# RS422_Breakout.net
KiCad netlist of a schematic drawn in Altium Designer
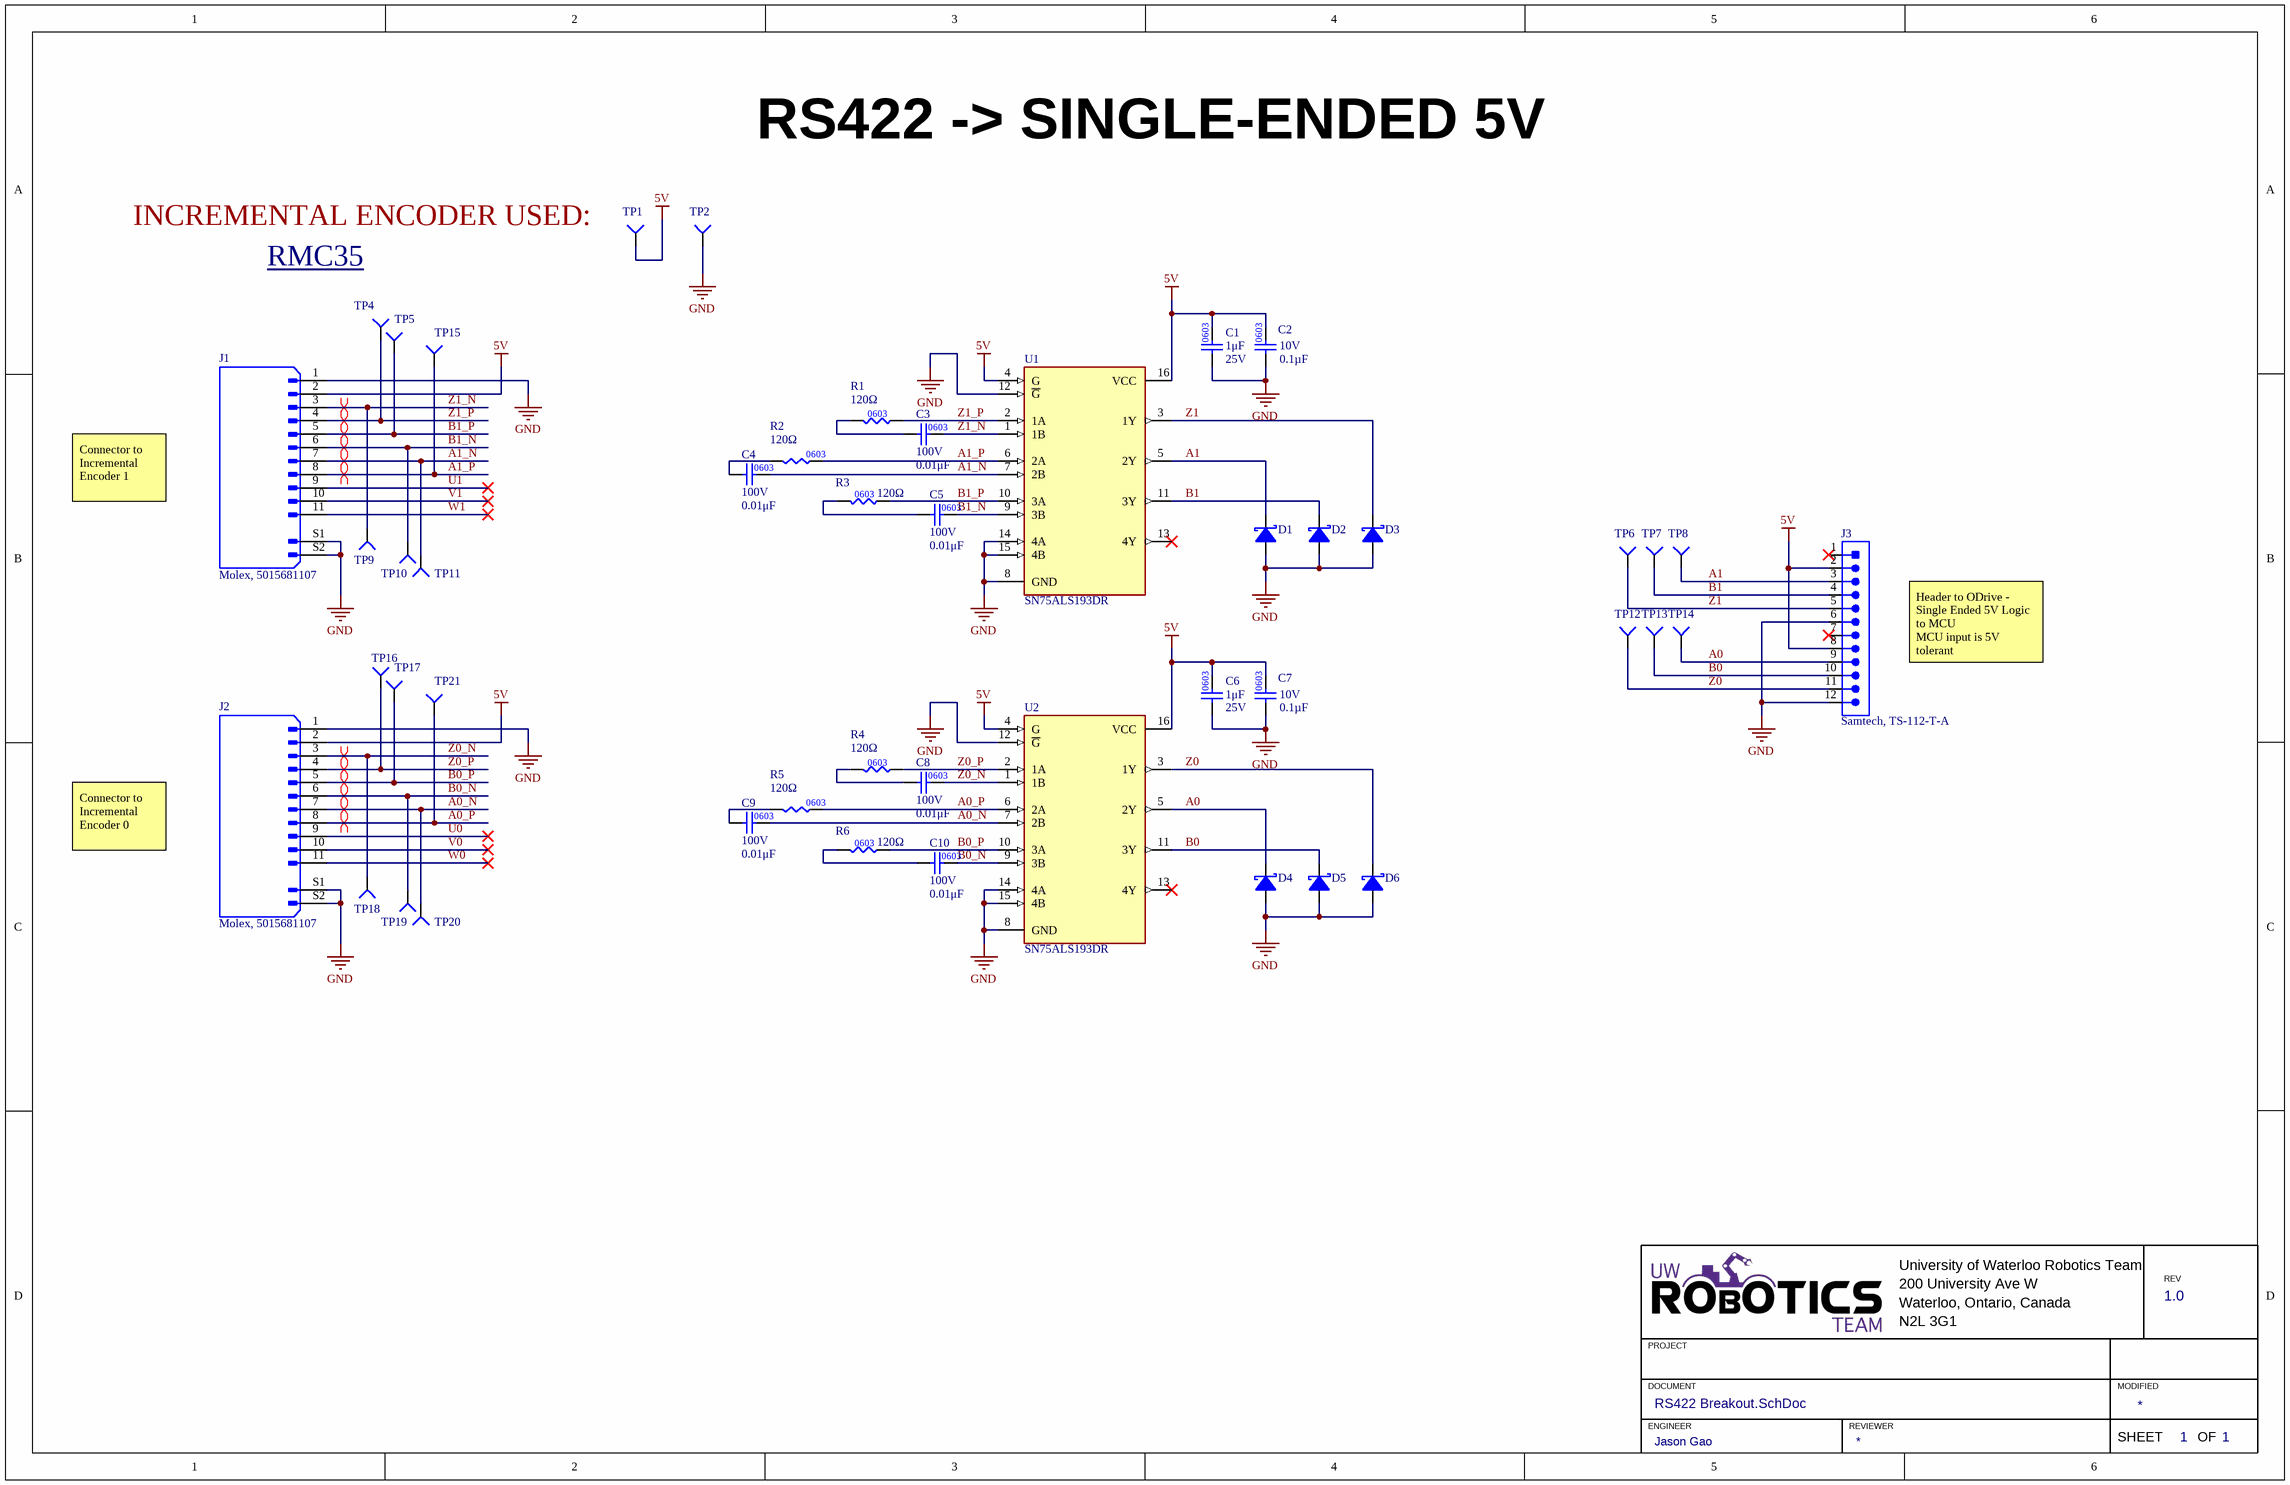
[diagram p0: RS422 Breakout.SchDoc]

(export (version "E")
  (design (tool "Eeschema 10.0.6"))
  (components
    (comp (ref "C1")
      (value "1μF")
      (footprint "CAP0603")
      (description "CAP CER 1UF 25V X5R 0603")
      (fields (field (name "VOLTAGE RATING") "25V") (field (name "Comment") "CAP_1uF_25V_0603"))
      (libsource (lib "UWRT_Schematic_Library_2020") (part "CAP_1uF_25V_0603"))
    )
    (comp (ref "C2")
      (value "0.1µF")
      (footprint "CAP0603")
      (description "CAP CER 0.1UF 10V X7R 0402")
      (fields (field (name "VOLTAGE RATING") "10V") (field (name "Comment") "CAP_0.1uF_10V_0603"))
      (libsource (lib "UWRT_Schematic_Library_2020") (part "CAP_0.1uF_10V_0603"))
    )
    (comp (ref "C3")
      (value "0.01μF")
      (footprint "CAP0603")
      (description "CAP CER 0.01uF 100V X7R 0603")
      (fields (field (name "VOLTAGE RATING") "100V") (field (name "Comment") "CAP_0.01uF_100V_0603"))
      (libsource (lib "UWRT_Schematic_Library_2020") (part "CAP_0.01uF_100V_0603"))
    )
    (comp (ref "C4")
      (value "0.01μF")
      (footprint "CAP0603")
      (description "CAP CER 0.01uF 100V X7R 0603")
      (fields (field (name "VOLTAGE RATING") "100V") (field (name "Comment") "CAP_0.01uF_100V_0603"))
      (libsource (lib "UWRT_Schematic_Library_2020") (part "CAP_0.01uF_100V_0603"))
    )
    (comp (ref "C5")
      (value "0.01μF")
      (footprint "CAP0603")
      (description "CAP CER 0.01uF 100V X7R 0603")
      (fields (field (name "VOLTAGE RATING") "100V") (field (name "Comment") "CAP_0.01uF_100V_0603"))
      (libsource (lib "UWRT_Schematic_Library_2020") (part "CAP_0.01uF_100V_0603"))
    )
    (comp (ref "C6")
      (value "1μF")
      (footprint "CAP0603")
      (description "CAP CER 1UF 25V X5R 0603")
      (fields (field (name "VOLTAGE RATING") "25V") (field (name "Comment") "CAP_1uF_25V_0603"))
      (libsource (lib "UWRT_Schematic_Library_2020") (part "CAP_1uF_25V_0603"))
    )
    (comp (ref "C7")
      (value "0.1µF")
      (footprint "CAP0603")
      (description "CAP CER 0.1UF 10V X7R 0402")
      (fields (field (name "VOLTAGE RATING") "10V") (field (name "Comment") "CAP_0.1uF_10V_0603"))
      (libsource (lib "UWRT_Schematic_Library_2020") (part "CAP_0.1uF_10V_0603"))
    )
    (comp (ref "C8")
      (value "0.01μF")
      (footprint "CAP0603")
      (description "CAP CER 0.01uF 100V X7R 0603")
      (fields (field (name "VOLTAGE RATING") "100V") (field (name "Comment") "CAP_0.01uF_100V_0603"))
      (libsource (lib "UWRT_Schematic_Library_2020") (part "CAP_0.01uF_100V_0603"))
    )
    (comp (ref "C9")
      (value "0.01μF")
      (footprint "CAP0603")
      (description "CAP CER 0.01uF 100V X7R 0603")
      (fields (field (name "VOLTAGE RATING") "100V") (field (name "Comment") "CAP_0.01uF_100V_0603"))
      (libsource (lib "UWRT_Schematic_Library_2020") (part "CAP_0.01uF_100V_0603"))
    )
    (comp (ref "C10")
      (value "0.01μF")
      (footprint "CAP0603")
      (description "CAP CER 0.01uF 100V X7R 0603")
      (fields (field (name "VOLTAGE RATING") "100V") (field (name "Comment") "CAP_0.01uF_100V_0603"))
      (libsource (lib "UWRT_Schematic_Library_2020") (part "CAP_0.01uF_100V_0603"))
    )
    (comp (ref "D1")
      (value "TVS_DIODE_UNIDIR_5V")
      (footprint "sod-923")
      (description "TVS DIODE 5VWM 12.3VC SOD923")
      (libsource (lib "UWRT_Schematic_Library_2020") (part "TVS_DIODE_UNIDIR_5V"))
    )
    (comp (ref "D2")
      (value "TVS_DIODE_UNIDIR_5V")
      (footprint "sod-923")
      (description "TVS DIODE 5VWM 12.3VC SOD923")
      (libsource (lib "UWRT_Schematic_Library_2020") (part "TVS_DIODE_UNIDIR_5V"))
    )
    (comp (ref "D3")
      (value "TVS_DIODE_UNIDIR_5V")
      (footprint "sod-923")
      (description "TVS DIODE 5VWM 12.3VC SOD923")
      (libsource (lib "UWRT_Schematic_Library_2020") (part "TVS_DIODE_UNIDIR_5V"))
    )
    (comp (ref "D4")
      (value "TVS_DIODE_UNIDIR_5V")
      (footprint "sod-923")
      (description "TVS DIODE 5VWM 12.3VC SOD923")
      (libsource (lib "UWRT_Schematic_Library_2020") (part "TVS_DIODE_UNIDIR_5V"))
    )
    (comp (ref "D5")
      (value "TVS_DIODE_UNIDIR_5V")
      (footprint "sod-923")
      (description "TVS DIODE 5VWM 12.3VC SOD923")
      (libsource (lib "UWRT_Schematic_Library_2020") (part "TVS_DIODE_UNIDIR_5V"))
    )
    (comp (ref "D6")
      (value "TVS_DIODE_UNIDIR_5V")
      (footprint "sod-923")
      (description "TVS DIODE 5VWM 12.3VC SOD923")
      (libsource (lib "UWRT_Schematic_Library_2020") (part "TVS_DIODE_UNIDIR_5V"))
    )
    (comp (ref "J1")
      (value "CON_12M_SM_RA")
      (footprint "MOLEX-5015681107")
      (description "CONN HEADER SMD RIGHT ANGLE 1MM PITCH")
      (fields (field (name "MP") "Molex, 5015681107"))
      (libsource (lib "templocal") (part "CON_11M_SM_RA"))
    )
    (comp (ref "J2")
      (value "CON_12M_SM_RA")
      (footprint "MOLEX-5015681107")
      (description "CONN HEADER SMD RIGHT ANGLE 1MM PITCH")
      (fields (field (name "MP") "Molex, 5015681107"))
      (libsource (lib "templocal") (part "CON_11M_SM_RA"))
    )
    (comp (ref "J3")
      (value "Samtech, TS-112-T-A")
      (footprint "Samtech-TS-112-T-A")
      (description "CONN HEADER THROUGH HOLE VERTICAL 2.54MM PITCH")
      (fields (field (name "MANUFACTURING PART NUMBER") "Samtech, TS-112-T-A"))
      (libsource (lib "UWRT_Schematic_Library_2020") (part "CON_12M_TH_VERT_2.54mm"))
    )
    (comp (ref "R1")
      (value "120Ω")
      (footprint "RES0603")
      (description "RES 120 OHM 5% 1/10W 0603")
      (fields (field (name "Comment") "RES_120Ω_0603_5%"))
      (libsource (lib "UWRT_Schematic_Library_2020") (part "RES_120Ω_0603_5%"))
    )
    (comp (ref "R2")
      (value "120Ω")
      (footprint "RES0603")
      (description "RES 120 OHM 5% 1/10W 0603")
      (fields (field (name "Comment") "RES_120Ω_0603_5%"))
      (libsource (lib "UWRT_Schematic_Library_2020") (part "RES_120Ω_0603_5%"))
    )
    (comp (ref "R3")
      (value "120Ω")
      (footprint "RES0603")
      (description "RES 120 OHM 5% 1/10W 0603")
      (fields (field (name "Comment") "RES_120Ω_0603_5%"))
      (libsource (lib "UWRT_Schematic_Library_2020") (part "RES_120Ω_0603_5%"))
    )
    (comp (ref "R4")
      (value "120Ω")
      (footprint "RES0603")
      (description "RES 120 OHM 5% 1/10W 0603")
      (fields (field (name "Comment") "RES_120Ω_0603_5%"))
      (libsource (lib "UWRT_Schematic_Library_2020") (part "RES_120Ω_0603_5%"))
    )
    (comp (ref "R5")
      (value "120Ω")
      (footprint "RES0603")
      (description "RES 120 OHM 5% 1/10W 0603")
      (fields (field (name "Comment") "RES_120Ω_0603_5%"))
      (libsource (lib "UWRT_Schematic_Library_2020") (part "RES_120Ω_0603_5%"))
    )
    (comp (ref "R6")
      (value "120Ω")
      (footprint "RES0603")
      (description "RES 120 OHM 5% 1/10W 0603")
      (fields (field (name "Comment") "RES_120Ω_0603_5%"))
      (libsource (lib "UWRT_Schematic_Library_2020") (part "RES_120Ω_0603_5%"))
    )
    (comp (ref "TP1")
      (value "TESTPOINT_SMD_LOOP")
      (footprint "S1751-46R")
      (description "TESTPOINT SMD LOOP")
      (libsource (lib "UWRT_Schematic_Library_2020") (part "TESTPOINT_SMD_LOOP"))
    )
    (comp (ref "TP2")
      (value "TESTPOINT_SMD_LOOP")
      (footprint "S1751-46R")
      (description "TESTPOINT SMD LOOP")
      (libsource (lib "UWRT_Schematic_Library_2020") (part "TESTPOINT_SMD_LOOP"))
    )
    (comp (ref "TP4")
      (value "TESTPOINT_1MM_SQUARE")
      (footprint "TESTPOINT_SQUARE_1MM")
      (description "TESTPOINT 1MM SQUARE")
      (libsource (lib "UWRT_Schematic_Library_2020") (part "TESTPOINT_1MM_SQUARE"))
    )
    (comp (ref "TP5")
      (value "TESTPOINT_1MM_SQUARE")
      (footprint "TESTPOINT_SQUARE_1MM")
      (description "TESTPOINT 1MM SQUARE")
      (libsource (lib "UWRT_Schematic_Library_2020") (part "TESTPOINT_1MM_SQUARE"))
    )
    (comp (ref "TP6")
      (value "TESTPOINT_1MM_CIRCLE")
      (footprint "TESTPOINT_CIRCLE_1MM")
      (description "TESTPOINT 1MM CIRCLE")
      (libsource (lib "UWRT_Schematic_Library_2020") (part "TESTPOINT_1MM_CIRCLE"))
    )
    (comp (ref "TP7")
      (value "TESTPOINT_1MM_CIRCLE")
      (footprint "TESTPOINT_CIRCLE_1MM")
      (description "TESTPOINT 1MM CIRCLE")
      (libsource (lib "UWRT_Schematic_Library_2020") (part "TESTPOINT_1MM_CIRCLE"))
    )
    (comp (ref "TP8")
      (value "TESTPOINT_1MM_CIRCLE")
      (footprint "TESTPOINT_CIRCLE_1MM")
      (description "TESTPOINT 1MM CIRCLE")
      (libsource (lib "UWRT_Schematic_Library_2020") (part "TESTPOINT_1MM_CIRCLE"))
    )
    (comp (ref "TP9")
      (value "TESTPOINT_1MM_CIRCLE")
      (footprint "TESTPOINT_CIRCLE_1MM")
      (description "TESTPOINT 1MM CIRCLE")
      (libsource (lib "UWRT_Schematic_Library_2020") (part "TESTPOINT_1MM_CIRCLE"))
    )
    (comp (ref "TP10")
      (value "TESTPOINT_1MM_CIRCLE")
      (footprint "TESTPOINT_CIRCLE_1MM")
      (description "TESTPOINT 1MM CIRCLE")
      (libsource (lib "UWRT_Schematic_Library_2020") (part "TESTPOINT_1MM_CIRCLE"))
    )
    (comp (ref "TP11")
      (value "TESTPOINT_1MM_CIRCLE")
      (footprint "TESTPOINT_CIRCLE_1MM")
      (description "TESTPOINT 1MM CIRCLE")
      (libsource (lib "UWRT_Schematic_Library_2020") (part "TESTPOINT_1MM_CIRCLE"))
    )
    (comp (ref "TP12")
      (value "TESTPOINT_1MM_CIRCLE")
      (footprint "TESTPOINT_CIRCLE_1MM")
      (description "TESTPOINT 1MM CIRCLE")
      (libsource (lib "UWRT_Schematic_Library_2020") (part "TESTPOINT_1MM_CIRCLE"))
    )
    (comp (ref "TP13")
      (value "TESTPOINT_1MM_CIRCLE")
      (footprint "TESTPOINT_CIRCLE_1MM")
      (description "TESTPOINT 1MM CIRCLE")
      (libsource (lib "UWRT_Schematic_Library_2020") (part "TESTPOINT_1MM_CIRCLE"))
    )
    (comp (ref "TP14")
      (value "TESTPOINT_1MM_CIRCLE")
      (footprint "TESTPOINT_CIRCLE_1MM")
      (description "TESTPOINT 1MM CIRCLE")
      (libsource (lib "UWRT_Schematic_Library_2020") (part "TESTPOINT_1MM_CIRCLE"))
    )
    (comp (ref "TP15")
      (value "TESTPOINT_1MM_SQUARE")
      (footprint "TESTPOINT_SQUARE_1MM")
      (description "TESTPOINT 1MM SQUARE")
      (libsource (lib "UWRT_Schematic_Library_2020") (part "TESTPOINT_1MM_SQUARE"))
    )
    (comp (ref "TP16")
      (value "TESTPOINT_1MM_SQUARE")
      (footprint "TESTPOINT_SQUARE_1MM")
      (description "TESTPOINT 1MM SQUARE")
      (libsource (lib "UWRT_Schematic_Library_2020") (part "TESTPOINT_1MM_SQUARE"))
    )
    (comp (ref "TP17")
      (value "TESTPOINT_1MM_SQUARE")
      (footprint "TESTPOINT_SQUARE_1MM")
      (description "TESTPOINT 1MM SQUARE")
      (libsource (lib "UWRT_Schematic_Library_2020") (part "TESTPOINT_1MM_SQUARE"))
    )
    (comp (ref "TP18")
      (value "TESTPOINT_1MM_CIRCLE")
      (footprint "TESTPOINT_CIRCLE_1MM")
      (description "TESTPOINT 1MM CIRCLE")
      (libsource (lib "UWRT_Schematic_Library_2020") (part "TESTPOINT_1MM_CIRCLE"))
    )
    (comp (ref "TP19")
      (value "TESTPOINT_1MM_CIRCLE")
      (footprint "TESTPOINT_CIRCLE_1MM")
      (description "TESTPOINT 1MM CIRCLE")
      (libsource (lib "UWRT_Schematic_Library_2020") (part "TESTPOINT_1MM_CIRCLE"))
    )
    (comp (ref "TP20")
      (value "TESTPOINT_1MM_CIRCLE")
      (footprint "TESTPOINT_CIRCLE_1MM")
      (description "TESTPOINT 1MM CIRCLE")
      (libsource (lib "UWRT_Schematic_Library_2020") (part "TESTPOINT_1MM_CIRCLE"))
    )
    (comp (ref "TP21")
      (value "TESTPOINT_1MM_SQUARE")
      (footprint "TESTPOINT_SQUARE_1MM")
      (description "TESTPOINT 1MM SQUARE")
      (libsource (lib "UWRT_Schematic_Library_2020") (part "TESTPOINT_1MM_SQUARE"))
    )
    (comp (ref "U1")
      (value "SN75ALS193DR")
      (footprint "SOIC127P600X175-16N")
      (description "0/4 Receiver - RS422, RS423 16-SOIC")
      (fields (field (name "COPYRIGHT") "Copyright (C) 2021 Ultra Librarian. All rights reserved."))
      (libsource (lib "UWRT_Schematic_Library_2020") (part "SN75ALS193DR"))
    )
    (comp (ref "U2")
      (value "SN75ALS193DR")
      (footprint "SOIC127P600X175-16N")
      (description "0/4 Receiver - RS422, RS423 16-SOIC")
      (fields (field (name "COPYRIGHT") "Copyright (C) 2021 Ultra Librarian. All rights reserved."))
      (libsource (lib "UWRT_Schematic_Library_2020") (part "SN75ALS193DR"))
    )
  )
  (nets
    (net (code "1") (name "/A0") (class "Default")
      (node (ref "D4") (pin "1") (pinfunction "Cathode_1") (pintype "passive"))
      (node (ref "J3") (pin "9") (pinfunction "3_9") (pintype "passive"))
      (node (ref "TP14") (pin "1") (pinfunction "=value_1") (pintype "passive"))
      (node (ref "U2") (pin "5") (pinfunction "2Y_5") (pintype "output"))
    )
    (net (code "2") (name "/A0_N") (class "Default")
      (node (ref "C9") (pin "2") (pinfunction "2_2") (pintype "passive"))
      (node (ref "J2") (pin "7") (pinfunction "7_7") (pintype "passive"))
      (node (ref "TP20") (pin "1") (pinfunction "=value_1") (pintype "passive"))
      (node (ref "U2") (pin "7") (pinfunction "2B_7") (pintype "input"))
    )
    (net (code "3") (name "/A0_P") (class "Default")
      (node (ref "J2") (pin "8") (pinfunction "8_8") (pintype "passive"))
      (node (ref "R5") (pin "2") (pinfunction "2_2") (pintype "passive"))
      (node (ref "TP21") (pin "1") (pinfunction "=value_1") (pintype "passive"))
      (node (ref "U2") (pin "6") (pinfunction "2A_6") (pintype "input"))
    )
    (net (code "4") (name "/A1") (class "Default")
      (node (ref "D1") (pin "1") (pinfunction "Cathode_1") (pintype "passive"))
      (node (ref "J3") (pin "3") (pinfunction "3_3") (pintype "passive"))
      (node (ref "TP8") (pin "1") (pinfunction "=value_1") (pintype "passive"))
      (node (ref "U1") (pin "5") (pinfunction "2Y_5") (pintype "output"))
    )
    (net (code "5") (name "/A1_N") (class "Default")
      (node (ref "C4") (pin "2") (pinfunction "2_2") (pintype "passive"))
      (node (ref "J1") (pin "7") (pinfunction "7_7") (pintype "passive"))
      (node (ref "TP11") (pin "1") (pinfunction "=value_1") (pintype "passive"))
      (node (ref "U1") (pin "7") (pinfunction "2B_7") (pintype "input"))
    )
    (net (code "6") (name "/A1_P") (class "Default")
      (node (ref "J1") (pin "8") (pinfunction "8_8") (pintype "passive"))
      (node (ref "R2") (pin "2") (pinfunction "2_2") (pintype "passive"))
      (node (ref "TP15") (pin "1") (pinfunction "=value_1") (pintype "passive"))
      (node (ref "U1") (pin "6") (pinfunction "2A_6") (pintype "input"))
    )
    (net (code "7") (name "/B0") (class "Default")
      (node (ref "D5") (pin "1") (pinfunction "Cathode_1") (pintype "passive"))
      (node (ref "J3") (pin "10") (pinfunction "4_10") (pintype "passive"))
      (node (ref "TP13") (pin "1") (pinfunction "=value_1") (pintype "passive"))
      (node (ref "U2") (pin "11") (pinfunction "3Y_11") (pintype "output"))
    )
    (net (code "8") (name "/B0_N") (class "Default")
      (node (ref "C10") (pin "2") (pinfunction "2_2") (pintype "passive"))
      (node (ref "J2") (pin "6") (pinfunction "6_6") (pintype "passive"))
      (node (ref "TP19") (pin "1") (pinfunction "=value_1") (pintype "passive"))
      (node (ref "U2") (pin "9") (pinfunction "3B_9") (pintype "input"))
    )
    (net (code "9") (name "/B0_P") (class "Default")
      (node (ref "J2") (pin "5") (pinfunction "5_5") (pintype "passive"))
      (node (ref "R6") (pin "1") (pinfunction "1_1") (pintype "passive"))
      (node (ref "TP17") (pin "1") (pinfunction "=value_1") (pintype "passive"))
      (node (ref "U2") (pin "10") (pinfunction "3A_10") (pintype "input"))
    )
    (net (code "10") (name "/B1") (class "Default")
      (node (ref "D2") (pin "1") (pinfunction "Cathode_1") (pintype "passive"))
      (node (ref "J3") (pin "4") (pinfunction "4_4") (pintype "passive"))
      (node (ref "TP7") (pin "1") (pinfunction "=value_1") (pintype "passive"))
      (node (ref "U1") (pin "11") (pinfunction "3Y_11") (pintype "output"))
    )
    (net (code "11") (name "/B1_N") (class "Default")
      (node (ref "C5") (pin "2") (pinfunction "2_2") (pintype "passive"))
      (node (ref "J1") (pin "6") (pinfunction "6_6") (pintype "passive"))
      (node (ref "TP10") (pin "1") (pinfunction "=value_1") (pintype "passive"))
      (node (ref "U1") (pin "9") (pinfunction "3B_9") (pintype "input"))
    )
    (net (code "12") (name "/B1_P") (class "Default")
      (node (ref "J1") (pin "5") (pinfunction "5_5") (pintype "passive"))
      (node (ref "R3") (pin "1") (pinfunction "1_1") (pintype "passive"))
      (node (ref "TP5") (pin "1") (pinfunction "=value_1") (pintype "passive"))
      (node (ref "U1") (pin "10") (pinfunction "3A_10") (pintype "input"))
    )
    (net (code "13") (name "/U0") (class "Default")
      (node (ref "J2") (pin "9") (pinfunction "9_9") (pintype "passive+no_connect"))
    )
    (net (code "14") (name "/U1") (class "Default")
      (node (ref "J1") (pin "9") (pinfunction "9_9") (pintype "passive+no_connect"))
    )
    (net (code "15") (name "/V0") (class "Default")
      (node (ref "J2") (pin "10") (pinfunction "10_10") (pintype "passive+no_connect"))
    )
    (net (code "16") (name "/V1") (class "Default")
      (node (ref "J1") (pin "10") (pinfunction "10_10") (pintype "passive+no_connect"))
    )
    (net (code "17") (name "/W0") (class "Default")
      (node (ref "J2") (pin "11") (pinfunction "11_11") (pintype "passive+no_connect"))
    )
    (net (code "18") (name "/W1") (class "Default")
      (node (ref "J1") (pin "11") (pinfunction "11_11") (pintype "passive+no_connect"))
    )
    (net (code "19") (name "/Z0") (class "Default")
      (node (ref "D6") (pin "1") (pinfunction "Cathode_1") (pintype "passive"))
      (node (ref "J3") (pin "11") (pinfunction "5_11") (pintype "passive"))
      (node (ref "TP12") (pin "1") (pinfunction "=value_1") (pintype "passive"))
      (node (ref "U2") (pin "3") (pinfunction "1Y_3") (pintype "output"))
    )
    (net (code "20") (name "/Z0_N") (class "Default")
      (node (ref "C8") (pin "2") (pinfunction "2_2") (pintype "passive"))
      (node (ref "J2") (pin "3") (pinfunction "3_3") (pintype "passive"))
      (node (ref "TP18") (pin "1") (pinfunction "=value_1") (pintype "passive"))
      (node (ref "U2") (pin "1") (pinfunction "1B_1") (pintype "input"))
    )
    (net (code "21") (name "/Z0_P") (class "Default")
      (node (ref "J2") (pin "4") (pinfunction "4_4") (pintype "passive"))
      (node (ref "R4") (pin "1") (pinfunction "1_1") (pintype "passive"))
      (node (ref "TP16") (pin "1") (pinfunction "=value_1") (pintype "passive"))
      (node (ref "U2") (pin "2") (pinfunction "1A_2") (pintype "input"))
    )
    (net (code "22") (name "/Z1") (class "Default")
      (node (ref "D3") (pin "1") (pinfunction "Cathode_1") (pintype "passive"))
      (node (ref "J3") (pin "5") (pinfunction "5_5") (pintype "passive"))
      (node (ref "TP6") (pin "1") (pinfunction "=value_1") (pintype "passive"))
      (node (ref "U1") (pin "3") (pinfunction "1Y_3") (pintype "output"))
    )
    (net (code "23") (name "/Z1_N") (class "Default")
      (node (ref "C3") (pin "2") (pinfunction "2_2") (pintype "passive"))
      (node (ref "J1") (pin "3") (pinfunction "3_3") (pintype "passive"))
      (node (ref "TP9") (pin "1") (pinfunction "=value_1") (pintype "passive"))
      (node (ref "U1") (pin "1") (pinfunction "1B_1") (pintype "input"))
    )
    (net (code "24") (name "/Z1_P") (class "Default")
      (node (ref "J1") (pin "4") (pinfunction "4_4") (pintype "passive"))
      (node (ref "R1") (pin "1") (pinfunction "1_1") (pintype "passive"))
      (node (ref "TP4") (pin "1") (pinfunction "=value_1") (pintype "passive"))
      (node (ref "U1") (pin "2") (pinfunction "1A_2") (pintype "input"))
    )
    (net (code "25") (name "5V") (class "Default")
      (node (ref "C1") (pin "2") (pinfunction "2_2") (pintype "passive"))
      (node (ref "C2") (pin "2") (pinfunction "2_2") (pintype "passive"))
      (node (ref "C6") (pin "2") (pinfunction "2_2") (pintype "passive"))
      (node (ref "C7") (pin "2") (pinfunction "2_2") (pintype "passive"))
      (node (ref "J1") (pin "2") (pinfunction "2_2") (pintype "passive"))
      (node (ref "J2") (pin "2") (pinfunction "2_2") (pintype "passive"))
      (node (ref "J3") (pin "2") (pinfunction "2_2") (pintype "passive"))
      (node (ref "J3") (pin "8") (pinfunction "2_8") (pintype "passive"))
      (node (ref "TP1") (pin "1") (pinfunction "=value_1") (pintype "passive"))
      (node (ref "U1") (pin "16") (pinfunction "VCC_16") (pintype "power_in"))
      (node (ref "U1") (pin "4") (pinfunction "G_4") (pintype "input"))
      (node (ref "U2") (pin "16") (pinfunction "VCC_16") (pintype "power_in"))
      (node (ref "U2") (pin "4") (pinfunction "G_4") (pintype "input"))
    )
    (net (code "26") (name "GND") (class "Default")
      (node (ref "C1") (pin "1") (pinfunction "1_1") (pintype "passive"))
      (node (ref "C2") (pin "1") (pinfunction "1_1") (pintype "passive"))
      (node (ref "C6") (pin "1") (pinfunction "1_1") (pintype "passive"))
      (node (ref "C7") (pin "1") (pinfunction "1_1") (pintype "passive"))
      (node (ref "D1") (pin "2") (pinfunction "Anode_2") (pintype "passive"))
      (node (ref "D2") (pin "2") (pinfunction "Anode_2") (pintype "passive"))
      (node (ref "D3") (pin "2") (pinfunction "Anode_2") (pintype "passive"))
      (node (ref "D4") (pin "2") (pinfunction "Anode_2") (pintype "passive"))
      (node (ref "D5") (pin "2") (pinfunction "Anode_2") (pintype "passive"))
      (node (ref "D6") (pin "2") (pinfunction "Anode_2") (pintype "passive"))
      (node (ref "J1") (pin "1") (pinfunction "1_1") (pintype "passive"))
      (node (ref "J1") (pin "S1") (pinfunction "SHIELD1_S1") (pintype "passive"))
      (node (ref "J1") (pin "S2") (pinfunction "SHIELD2_S2") (pintype "passive"))
      (node (ref "J2") (pin "1") (pinfunction "1_1") (pintype "passive"))
      (node (ref "J2") (pin "S1") (pinfunction "SHIELD1_S1") (pintype "passive"))
      (node (ref "J2") (pin "S2") (pinfunction "SHIELD2_S2") (pintype "passive"))
      (node (ref "J3") (pin "12") (pinfunction "6_12") (pintype "passive"))
      (node (ref "J3") (pin "6") (pinfunction "6_6") (pintype "passive"))
      (node (ref "TP2") (pin "1") (pinfunction "=value_1") (pintype "passive"))
      (node (ref "U1") (pin "12") (pinfunction "~{G}_12") (pintype "input"))
      (node (ref "U1") (pin "14") (pinfunction "4A_14") (pintype "input"))
      (node (ref "U1") (pin "15") (pinfunction "4B_15") (pintype "input"))
      (node (ref "U1") (pin "8") (pinfunction "GND_8") (pintype "power_in"))
      (node (ref "U2") (pin "12") (pinfunction "~{G}_12") (pintype "input"))
      (node (ref "U2") (pin "14") (pinfunction "4A_14") (pintype "input"))
      (node (ref "U2") (pin "15") (pinfunction "4B_15") (pintype "input"))
      (node (ref "U2") (pin "8") (pinfunction "GND_8") (pintype "power_in"))
    )
    (net (code "27") (name "Net-(C3-Pad1)") (class "Default")
      (node (ref "C3") (pin "1") (pinfunction "1_1") (pintype "passive"))
      (node (ref "R1") (pin "2") (pinfunction "2_2") (pintype "passive"))
    )
    (net (code "28") (name "Net-(C4-Pad1)") (class "Default")
      (node (ref "C4") (pin "1") (pinfunction "1_1") (pintype "passive"))
      (node (ref "R2") (pin "1") (pinfunction "1_1") (pintype "passive"))
    )
    (net (code "29") (name "Net-(C5-Pad1)") (class "Default")
      (node (ref "C5") (pin "1") (pinfunction "1_1") (pintype "passive"))
      (node (ref "R3") (pin "2") (pinfunction "2_2") (pintype "passive"))
    )
    (net (code "30") (name "Net-(C8-Pad1)") (class "Default")
      (node (ref "C8") (pin "1") (pinfunction "1_1") (pintype "passive"))
      (node (ref "R4") (pin "2") (pinfunction "2_2") (pintype "passive"))
    )
    (net (code "31") (name "Net-(C9-Pad1)") (class "Default")
      (node (ref "C9") (pin "1") (pinfunction "1_1") (pintype "passive"))
      (node (ref "R5") (pin "1") (pinfunction "1_1") (pintype "passive"))
    )
    (net (code "32") (name "Net-(C10-Pad1)") (class "Default")
      (node (ref "C10") (pin "1") (pinfunction "1_1") (pintype "passive"))
      (node (ref "R6") (pin "2") (pinfunction "2_2") (pintype "passive"))
    )
    (net (code "33") (name "unconnected-(J3-1-Pad7)") (class "Default")
      (node (ref "J3") (pin "7") (pinfunction "1_7") (pintype "passive+no_connect"))
    )
    (net (code "34") (name "unconnected-(J3-Pad1)") (class "Default")
      (node (ref "J3") (pin "1") (pinfunction "1_1") (pintype "passive+no_connect"))
    )
    (net (code "35") (name "unconnected-(U1-4Y-Pad13)") (class "Default")
      (node (ref "U1") (pin "13") (pinfunction "4Y_13") (pintype "output+no_connect"))
    )
    (net (code "36") (name "unconnected-(U2-4Y-Pad13)") (class "Default")
      (node (ref "U2") (pin "13") (pinfunction "4Y_13") (pintype "output+no_connect"))
    )
  )
)
